# LIDO-HW_100_OutputStage.net
KiCad netlist of a schematic drawn in Altium Designer
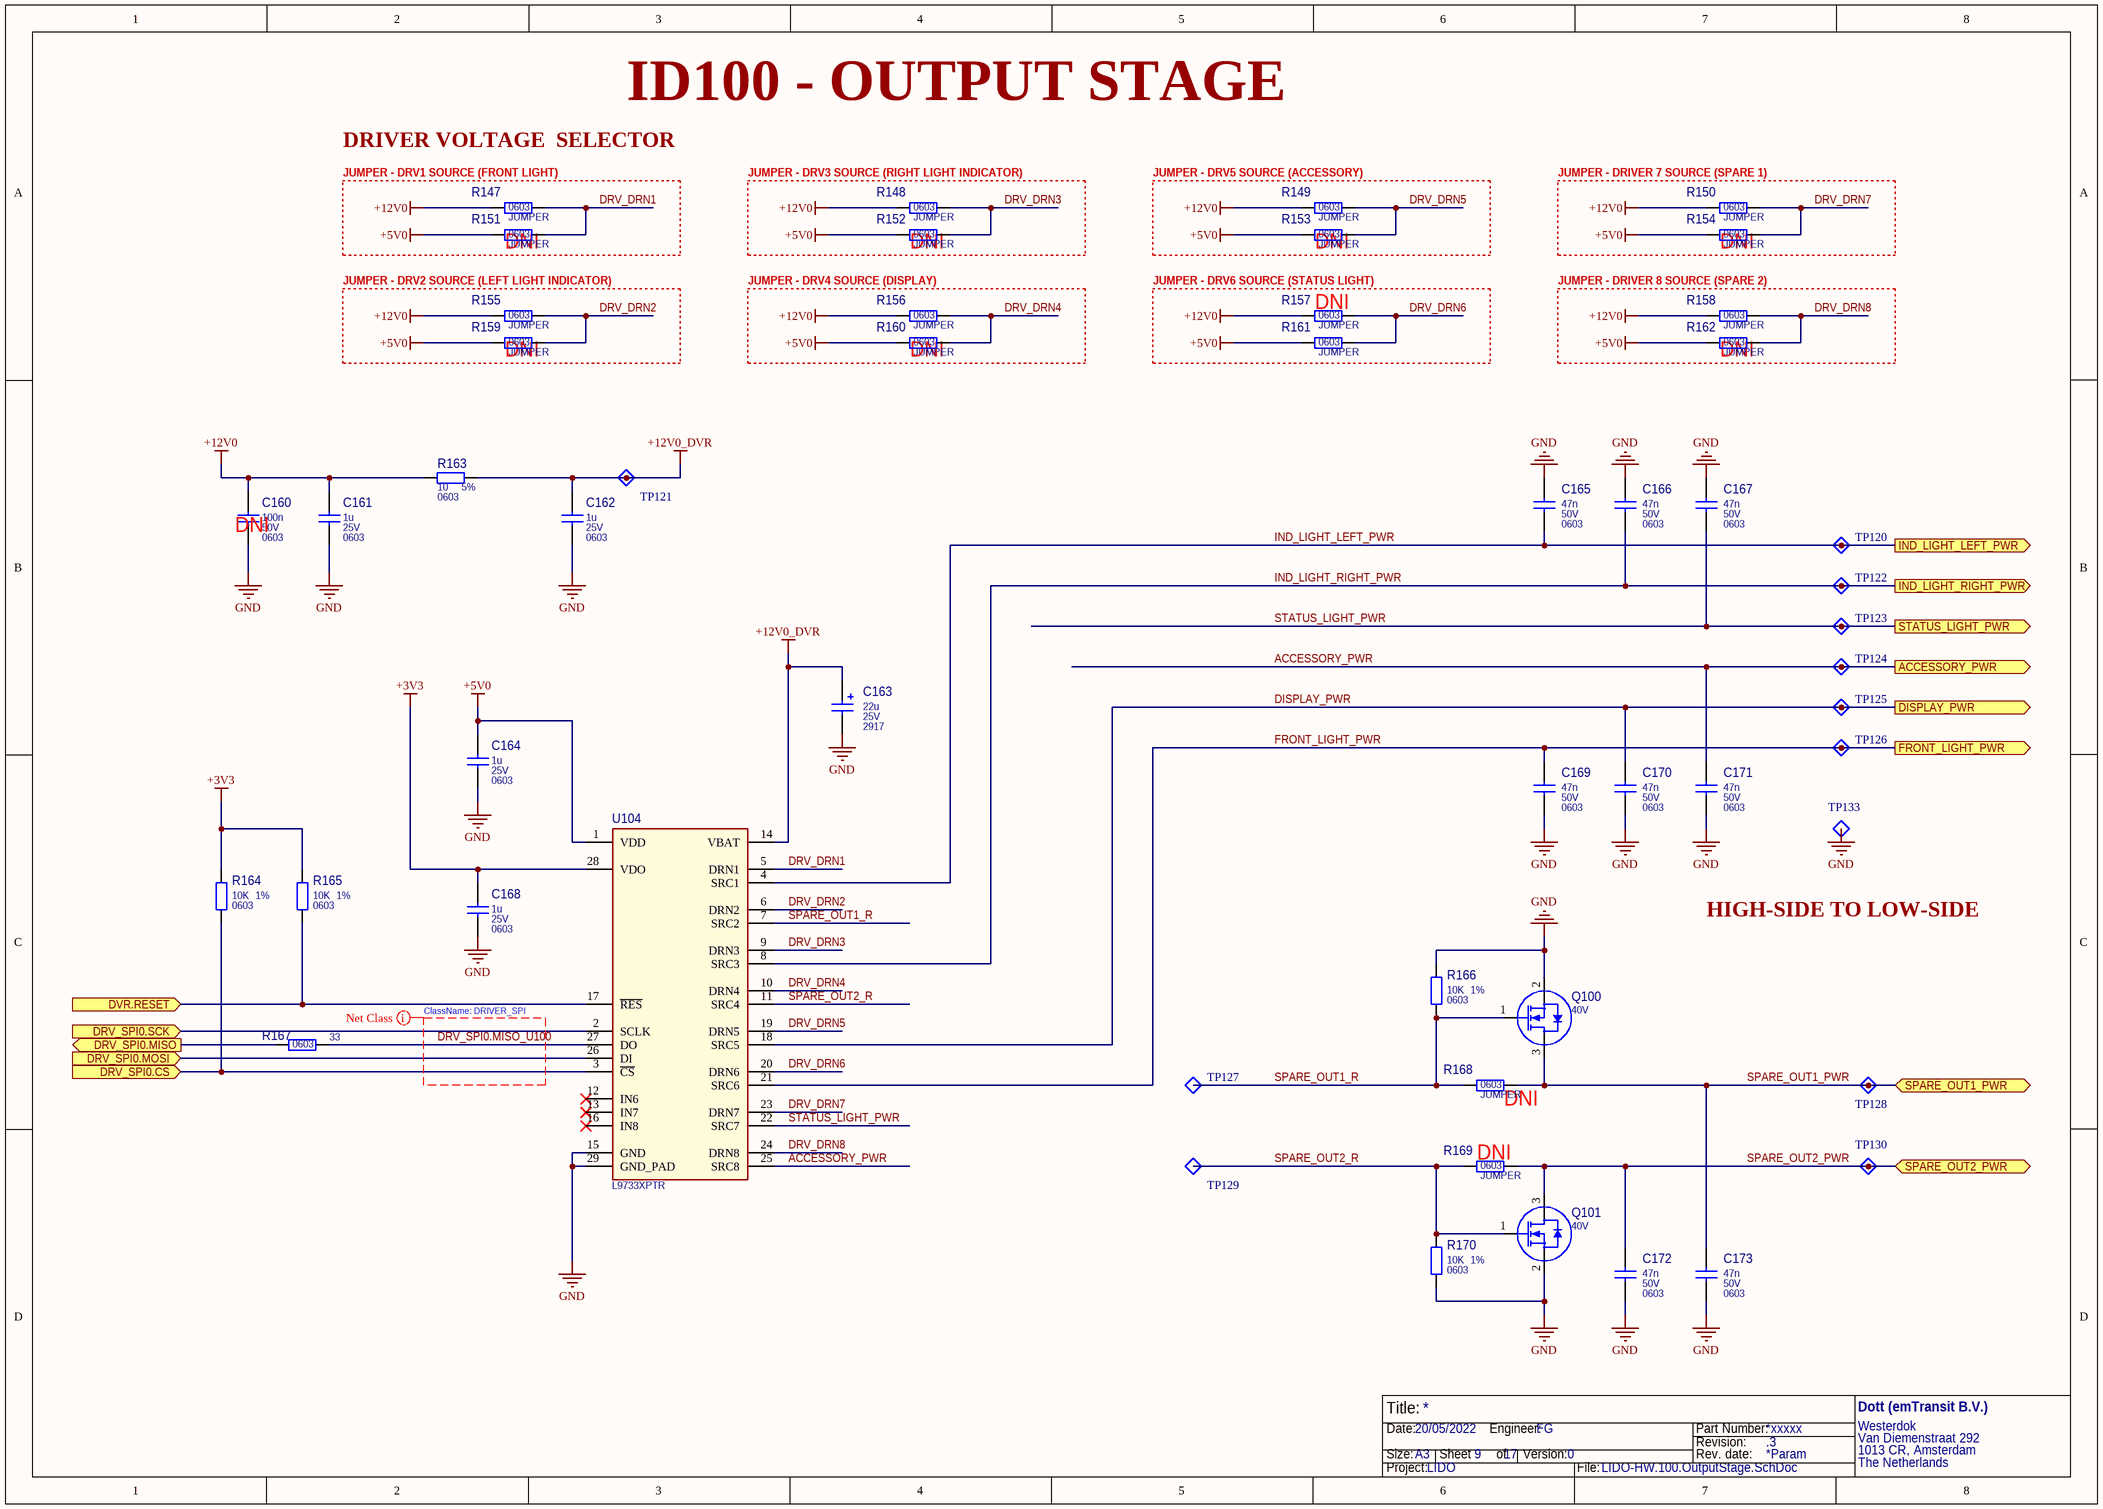
[diagram p0: LIDO-HW.100.OutputStage.SchDoc]

(export (version "E")
  (design (tool "Eeschema 10.0.6"))
  (components
    (comp (ref "C160")
      (value "100n")
      (footprint "CAP_0603_1608X90-N_MURATA_A")
      (description "CAP CER 0.1UF 50V X7R 0603")
      (fields
        (field (name "MANUFACTURER PART NUMBER") "CGA3E2X7R1H104K080AA")
        (field (name "MANUFACTURER") "TDK Corporation")
        (field (name "PART VALUE 2") "50V")
        (field (name "PART PACKAGE") "0603")
      )
      (libsource (lib "DB_Library") (part "Ceramic"))
    )
    (comp (ref "C161")
      (value "1u")
      (footprint "CAP_0603_1608X90-N_MURATA_A")
      (description "CAP CER 1UF 25V X7R 0603")
      (fields
        (field (name "MANUFACTURER PART NUMBER") "CGA3E1X7R1E105M080AE")
        (field (name "MANUFACTURER") "TDK Corporation")
        (field (name "PART VALUE 2") "25V")
        (field (name "PART PACKAGE") "0603")
      )
      (libsource (lib "DB_Library") (part "Ceramic"))
    )
    (comp (ref "C162")
      (value "1u")
      (footprint "CAP_0603_1608X90-N_MURATA_A")
      (description "CAP CER 1UF 25V X7R 0603")
      (fields
        (field (name "MANUFACTURER PART NUMBER") "CGA3E1X7R1E105M080AE")
        (field (name "MANUFACTURER") "TDK Corporation")
        (field (name "PART VALUE 2") "25V")
        (field (name "PART PACKAGE") "0603")
      )
      (libsource (lib "DB_Library") (part "Ceramic"))
    )
    (comp (ref "C163")
      (value "22u")
      (footprint "CAP_2917_7343X140-N_MURATA_A")
      (description "CAP ALUM POLY 22UF 20% 25V SMD")
      (fields
        (field (name "MANUFACTURER PART NUMBER") "ECASD31E226M040KA0")
        (field (name "MANUFACTURER") "Murata Electronics")
        (field (name "PART VALUE 2") "25V")
        (field (name "PART PACKAGE") "2917")
      )
      (libsource (lib "DB_Library") (part "Polarized"))
    )
    (comp (ref "C164")
      (value "1u")
      (footprint "CAP_0603_1608X90-N_MURATA_A")
      (description "CAP CER 1UF 25V X7R 0603")
      (fields
        (field (name "MANUFACTURER PART NUMBER") "CGA3E1X7R1E105M080AE")
        (field (name "MANUFACTURER") "TDK Corporation")
        (field (name "PART VALUE 2") "25V")
        (field (name "PART PACKAGE") "0603")
      )
      (libsource (lib "DB_Library") (part "Ceramic"))
    )
    (comp (ref "C165")
      (value "47n")
      (footprint "CAP_0603_1608X90-N_MURATA_A")
      (description "CAP CER 0.047UF 50V X7R 0603")
      (fields
        (field (name "MANUFACTURER PART NUMBER") "GCM188R71H473KA55D")
        (field (name "MANUFACTURER") "Murata Electronics")
        (field (name "PART VALUE 2") "50V")
        (field (name "PART PACKAGE") "0603")
      )
      (libsource (lib "DB_Library") (part "Ceramic"))
    )
    (comp (ref "C166")
      (value "47n")
      (footprint "CAP_0603_1608X90-N_MURATA_A")
      (description "CAP CER 0.047UF 50V X7R 0603")
      (fields
        (field (name "MANUFACTURER PART NUMBER") "GCM188R71H473KA55D")
        (field (name "MANUFACTURER") "Murata Electronics")
        (field (name "PART VALUE 2") "50V")
        (field (name "PART PACKAGE") "0603")
      )
      (libsource (lib "DB_Library") (part "Ceramic"))
    )
    (comp (ref "C167")
      (value "47n")
      (footprint "CAP_0603_1608X90-N_MURATA_A")
      (description "CAP CER 0.047UF 50V X7R 0603")
      (fields
        (field (name "MANUFACTURER PART NUMBER") "GCM188R71H473KA55D")
        (field (name "MANUFACTURER") "Murata Electronics")
        (field (name "PART VALUE 2") "50V")
        (field (name "PART PACKAGE") "0603")
      )
      (libsource (lib "DB_Library") (part "Ceramic"))
    )
    (comp (ref "C168")
      (value "1u")
      (footprint "CAP_0603_1608X90-N_MURATA_A")
      (description "CAP CER 1UF 25V X7R 0603")
      (fields
        (field (name "MANUFACTURER PART NUMBER") "CGA3E1X7R1E105M080AE")
        (field (name "MANUFACTURER") "TDK Corporation")
        (field (name "PART VALUE 2") "25V")
        (field (name "PART PACKAGE") "0603")
      )
      (libsource (lib "DB_Library") (part "Ceramic"))
    )
    (comp (ref "C169")
      (value "47n")
      (footprint "CAP_0603_1608X90-N_MURATA_A")
      (description "CAP CER 0.047UF 50V X7R 0603")
      (fields
        (field (name "MANUFACTURER PART NUMBER") "GCM188R71H473KA55D")
        (field (name "MANUFACTURER") "Murata Electronics")
        (field (name "PART VALUE 2") "50V")
        (field (name "PART PACKAGE") "0603")
      )
      (libsource (lib "DB_Library") (part "Ceramic"))
    )
    (comp (ref "C170")
      (value "47n")
      (footprint "CAP_0603_1608X90-N_MURATA_A")
      (description "CAP CER 0.047UF 50V X7R 0603")
      (fields
        (field (name "MANUFACTURER PART NUMBER") "GCM188R71H473KA55D")
        (field (name "MANUFACTURER") "Murata Electronics")
        (field (name "PART VALUE 2") "50V")
        (field (name "PART PACKAGE") "0603")
      )
      (libsource (lib "DB_Library") (part "Ceramic"))
    )
    (comp (ref "C171")
      (value "47n")
      (footprint "CAP_0603_1608X90-N_MURATA_A")
      (description "CAP CER 0.047UF 50V X7R 0603")
      (fields
        (field (name "MANUFACTURER PART NUMBER") "GCM188R71H473KA55D")
        (field (name "MANUFACTURER") "Murata Electronics")
        (field (name "PART VALUE 2") "50V")
        (field (name "PART PACKAGE") "0603")
      )
      (libsource (lib "DB_Library") (part "Ceramic"))
    )
    (comp (ref "C172")
      (value "47n")
      (footprint "CAP_0603_1608X90-N_MURATA_A")
      (description "CAP CER 0.047UF 50V X7R 0603")
      (fields
        (field (name "MANUFACTURER PART NUMBER") "GCM188R71H473KA55D")
        (field (name "MANUFACTURER") "Murata Electronics")
        (field (name "PART VALUE 2") "50V")
        (field (name "PART PACKAGE") "0603")
      )
      (libsource (lib "DB_Library") (part "Ceramic"))
    )
    (comp (ref "C173")
      (value "47n")
      (footprint "CAP_0603_1608X90-N_MURATA_A")
      (description "CAP CER 0.047UF 50V X7R 0603")
      (fields
        (field (name "MANUFACTURER PART NUMBER") "GCM188R71H473KA55D")
        (field (name "MANUFACTURER") "Murata Electronics")
        (field (name "PART VALUE 2") "50V")
        (field (name "PART PACKAGE") "0603")
      )
      (libsource (lib "DB_Library") (part "Ceramic"))
    )
    (comp (ref "Q100")
      (value "40V")
      (footprint "SOT23-3P95_237X112L60-N_ANALOG_A")
      (description "MOSFET N-CH 40V 4.6A SOT23")
      (fields
        (field (name "MANUFACTURER PART NUMBER") "DMN4035LQ-13")
        (field (name "MANUFACTURER") "Diodes Incorporated")
      )
      (libsource (lib "DB_Library") (part "MOSFET_N_WD_1G_2S_3D"))
    )
    (comp (ref "Q101")
      (value "40V")
      (footprint "SOT23-3P95_237X112L60-N_ANALOG_A")
      (description "MOSFET N-CH 40V 4.6A SOT23")
      (fields
        (field (name "MANUFACTURER PART NUMBER") "DMN4035LQ-13")
        (field (name "MANUFACTURER") "Diodes Incorporated")
      )
      (libsource (lib "DB_Library") (part "MOSFET_N_WD_1G_2S_3D"))
    )
    (comp (ref "R147")
      (value "JUMPER")
      (footprint "RES_0603_1608X60-N_YAGEO_A")
      (description "RES 0 OHM JUMPER 1/10W 0603")
      (fields
        (field (name "MANUFACTURER PART NUMBER") "RC0603JR-070RL")
        (field (name "MANUFACTURER") "YAGEO")
        (field (name "PART PACKAGE") "0603")
      )
      (libsource (lib "DB_Library") (part "Resistor"))
    )
    (comp (ref "R148")
      (value "JUMPER")
      (footprint "RES_0603_1608X60-N_YAGEO_A")
      (description "RES 0 OHM JUMPER 1/10W 0603")
      (fields
        (field (name "MANUFACTURER PART NUMBER") "RC0603JR-070RL")
        (field (name "MANUFACTURER") "YAGEO")
        (field (name "PART PACKAGE") "0603")
      )
      (libsource (lib "DB_Library") (part "Resistor"))
    )
    (comp (ref "R149")
      (value "JUMPER")
      (footprint "RES_0603_1608X60-N_YAGEO_A")
      (description "RES 0 OHM JUMPER 1/10W 0603")
      (fields
        (field (name "MANUFACTURER PART NUMBER") "RC0603JR-070RL")
        (field (name "MANUFACTURER") "YAGEO")
        (field (name "PART PACKAGE") "0603")
      )
      (libsource (lib "DB_Library") (part "Resistor"))
    )
    (comp (ref "R150")
      (value "JUMPER")
      (footprint "RES_0603_1608X60-N_YAGEO_A")
      (description "RES 0 OHM JUMPER 1/10W 0603")
      (fields
        (field (name "MANUFACTURER PART NUMBER") "RC0603JR-070RL")
        (field (name "MANUFACTURER") "YAGEO")
        (field (name "PART PACKAGE") "0603")
      )
      (libsource (lib "DB_Library") (part "Resistor"))
    )
    (comp (ref "R151")
      (value "JUMPER")
      (footprint "RES_0603_1608X60-N_YAGEO_A")
      (description "RES 0 OHM JUMPER 1/10W 0603")
      (fields
        (field (name "MANUFACTURER PART NUMBER") "RC0603JR-070RL")
        (field (name "MANUFACTURER") "YAGEO")
        (field (name "PART PACKAGE") "0603")
      )
      (libsource (lib "DB_Library") (part "Resistor"))
    )
    (comp (ref "R152")
      (value "JUMPER")
      (footprint "RES_0603_1608X60-N_YAGEO_A")
      (description "RES 0 OHM JUMPER 1/10W 0603")
      (fields
        (field (name "MANUFACTURER PART NUMBER") "RC0603JR-070RL")
        (field (name "MANUFACTURER") "YAGEO")
        (field (name "PART PACKAGE") "0603")
      )
      (libsource (lib "DB_Library") (part "Resistor"))
    )
    (comp (ref "R153")
      (value "JUMPER")
      (footprint "RES_0603_1608X60-N_YAGEO_A")
      (description "RES 0 OHM JUMPER 1/10W 0603")
      (fields
        (field (name "MANUFACTURER PART NUMBER") "RC0603JR-070RL")
        (field (name "MANUFACTURER") "YAGEO")
        (field (name "PART PACKAGE") "0603")
      )
      (libsource (lib "DB_Library") (part "Resistor"))
    )
    (comp (ref "R154")
      (value "JUMPER")
      (footprint "RES_0603_1608X60-N_YAGEO_A")
      (description "RES 0 OHM JUMPER 1/10W 0603")
      (fields
        (field (name "MANUFACTURER PART NUMBER") "RC0603JR-070RL")
        (field (name "MANUFACTURER") "YAGEO")
        (field (name "PART PACKAGE") "0603")
      )
      (libsource (lib "DB_Library") (part "Resistor"))
    )
    (comp (ref "R155")
      (value "JUMPER")
      (footprint "RES_0603_1608X60-N_YAGEO_A")
      (description "RES 0 OHM JUMPER 1/10W 0603")
      (fields
        (field (name "MANUFACTURER PART NUMBER") "RC0603JR-070RL")
        (field (name "MANUFACTURER") "YAGEO")
        (field (name "PART PACKAGE") "0603")
      )
      (libsource (lib "DB_Library") (part "Resistor"))
    )
    (comp (ref "R156")
      (value "JUMPER")
      (footprint "RES_0603_1608X60-N_YAGEO_A")
      (description "RES 0 OHM JUMPER 1/10W 0603")
      (fields
        (field (name "MANUFACTURER PART NUMBER") "RC0603JR-070RL")
        (field (name "MANUFACTURER") "YAGEO")
        (field (name "PART PACKAGE") "0603")
      )
      (libsource (lib "DB_Library") (part "Resistor"))
    )
    (comp (ref "R157")
      (value "JUMPER")
      (footprint "RES_0603_1608X60-N_YAGEO_A")
      (description "RES 0 OHM JUMPER 1/10W 0603")
      (fields
        (field (name "MANUFACTURER PART NUMBER") "RC0603JR-070RL")
        (field (name "MANUFACTURER") "YAGEO")
        (field (name "PART PACKAGE") "0603")
      )
      (libsource (lib "DB_Library") (part "Resistor"))
    )
    (comp (ref "R158")
      (value "JUMPER")
      (footprint "RES_0603_1608X60-N_YAGEO_A")
      (description "RES 0 OHM JUMPER 1/10W 0603")
      (fields
        (field (name "MANUFACTURER PART NUMBER") "RC0603JR-070RL")
        (field (name "MANUFACTURER") "YAGEO")
        (field (name "PART PACKAGE") "0603")
      )
      (libsource (lib "DB_Library") (part "Resistor"))
    )
    (comp (ref "R159")
      (value "JUMPER")
      (footprint "RES_0603_1608X60-N_YAGEO_A")
      (description "RES 0 OHM JUMPER 1/10W 0603")
      (fields
        (field (name "MANUFACTURER PART NUMBER") "RC0603JR-070RL")
        (field (name "MANUFACTURER") "YAGEO")
        (field (name "PART PACKAGE") "0603")
      )
      (libsource (lib "DB_Library") (part "Resistor"))
    )
    (comp (ref "R160")
      (value "JUMPER")
      (footprint "RES_0603_1608X60-N_YAGEO_A")
      (description "RES 0 OHM JUMPER 1/10W 0603")
      (fields
        (field (name "MANUFACTURER PART NUMBER") "RC0603JR-070RL")
        (field (name "MANUFACTURER") "YAGEO")
        (field (name "PART PACKAGE") "0603")
      )
      (libsource (lib "DB_Library") (part "Resistor"))
    )
    (comp (ref "R161")
      (value "JUMPER")
      (footprint "RES_0603_1608X60-N_YAGEO_A")
      (description "RES 0 OHM JUMPER 1/10W 0603")
      (fields
        (field (name "MANUFACTURER PART NUMBER") "RC0603JR-070RL")
        (field (name "MANUFACTURER") "YAGEO")
        (field (name "PART PACKAGE") "0603")
      )
      (libsource (lib "DB_Library") (part "Resistor"))
    )
    (comp (ref "R162")
      (value "JUMPER")
      (footprint "RES_0603_1608X60-N_YAGEO_A")
      (description "RES 0 OHM JUMPER 1/10W 0603")
      (fields
        (field (name "MANUFACTURER PART NUMBER") "RC0603JR-070RL")
        (field (name "MANUFACTURER") "YAGEO")
        (field (name "PART PACKAGE") "0603")
      )
      (libsource (lib "DB_Library") (part "Resistor"))
    )
    (comp (ref "R163")
      (value "10")
      (footprint "RES_0603_1608X60-N_YAGEO_A")
      (description "RES SMD 10 OHM 5% 1/4W 0603")
      (fields
        (field (name "MANUFACTURER PART NUMBER") "ESR03EZPJ100")
        (field (name "MANUFACTURER") "Rohm Semiconductor")
        (field (name "PART VALUE 2") "5%")
        (field (name "PART PACKAGE") "0603")
      )
      (libsource (lib "DB_Library") (part "Resistor"))
    )
    (comp (ref "R164")
      (value "10K")
      (footprint "RES_0603_1608X60-N_YAGEO_A")
      (description "RES 10K OHM 1% 1/10W 0603")
      (fields
        (field (name "MANUFACTURER PART NUMBER") "RC0603FR-0710KL")
        (field (name "MANUFACTURER") "YAGEO")
        (field (name "PART VALUE 2") "1%")
        (field (name "PART PACKAGE") "0603")
      )
      (libsource (lib "") (part "Resistor_1"))
    )
    (comp (ref "R165")
      (value "10K")
      (footprint "RES_0603_1608X60-N_YAGEO_A")
      (description "RES 10K OHM 1% 1/10W 0603")
      (fields
        (field (name "MANUFACTURER PART NUMBER") "RC0603FR-0710KL")
        (field (name "MANUFACTURER") "YAGEO")
        (field (name "PART VALUE 2") "1%")
        (field (name "PART PACKAGE") "0603")
      )
      (libsource (lib "") (part "Resistor_1"))
    )
    (comp (ref "R166")
      (value "10K")
      (footprint "RES_0603_1608X60-N_YAGEO_A")
      (description "RES 10K OHM 1% 1/10W 0603")
      (fields
        (field (name "MANUFACTURER PART NUMBER") "RC0603FR-0710KL")
        (field (name "MANUFACTURER") "YAGEO")
        (field (name "PART VALUE 2") "1%")
        (field (name "PART PACKAGE") "0603")
      )
      (libsource (lib "") (part "Resistor_1"))
    )
    (comp (ref "R167")
      (value "33")
      (footprint "RES_0603_1608X60-N_YAGEO_A")
      (description "RES 33 OHM 5% 1/10W 0603")
      (fields
        (field (name "MANUFACTURER PART NUMBER") "RC0603JR-0733RL")
        (field (name "MANUFACTURER") "YAGEO")
        (field (name "PART PACKAGE") "0603")
      )
      (libsource (lib "DB_Library") (part "Resistor"))
    )
    (comp (ref "R168")
      (value "JUMPER")
      (footprint "RES_0603_1608X60-N_YAGEO_A")
      (description "RES 0 OHM JUMPER 1/10W 0603")
      (fields
        (field (name "MANUFACTURER PART NUMBER") "RC0603JR-070RL")
        (field (name "MANUFACTURER") "YAGEO")
        (field (name "PART PACKAGE") "0603")
      )
      (libsource (lib "DB_Library") (part "Resistor"))
    )
    (comp (ref "R169")
      (value "JUMPER")
      (footprint "RES_0603_1608X60-N_YAGEO_A")
      (description "RES 0 OHM JUMPER 1/10W 0603")
      (fields
        (field (name "MANUFACTURER PART NUMBER") "RC0603JR-070RL")
        (field (name "MANUFACTURER") "YAGEO")
        (field (name "PART PACKAGE") "0603")
      )
      (libsource (lib "DB_Library") (part "Resistor"))
    )
    (comp (ref "R170")
      (value "10K")
      (footprint "RES_0603_1608X60-N_YAGEO_A")
      (description "RES 10K OHM 1% 1/10W 0603")
      (fields
        (field (name "MANUFACTURER PART NUMBER") "RC0603FR-0710KL")
        (field (name "MANUFACTURER") "YAGEO")
        (field (name "PART VALUE 2") "1%")
        (field (name "PART PACKAGE") "0603")
      )
      (libsource (lib "") (part "Resistor_1"))
    )
    (comp (ref "TP120")
      (value "TestPoint_A")
      (footprint "TESTPOINT_1D_A")
      (description "Pad Diamater 1mm")
      (fields (field (name "PART") "Test Point 1D A") (field (name "OBSOLETE PART") "False"))
      (libsource (lib "DB_Library") (part "TestPoint_A"))
    )
    (comp (ref "TP121")
      (value "TestPoint_A")
      (footprint "TESTPOINT_1D_A")
      (description "Pad Diamater 1mm")
      (fields (field (name "PART") "Test Point 1D A") (field (name "OBSOLETE PART") "False"))
      (libsource (lib "DB_Library") (part "TestPoint_A"))
    )
    (comp (ref "TP122")
      (value "TestPoint_A")
      (footprint "TESTPOINT_1D_A")
      (description "Pad Diamater 1mm")
      (fields (field (name "PART") "Test Point 1D A") (field (name "OBSOLETE PART") "False"))
      (libsource (lib "DB_Library") (part "TestPoint_A"))
    )
    (comp (ref "TP123")
      (value "TestPoint_A")
      (footprint "TESTPOINT_1D_A")
      (description "Pad Diamater 1mm")
      (fields (field (name "PART") "Test Point 1D A") (field (name "OBSOLETE PART") "False"))
      (libsource (lib "DB_Library") (part "TestPoint_A"))
    )
    (comp (ref "TP124")
      (value "TestPoint_A")
      (footprint "TESTPOINT_1D_A")
      (description "Pad Diamater 1mm")
      (fields (field (name "PART") "Test Point 1D A") (field (name "OBSOLETE PART") "False"))
      (libsource (lib "DB_Library") (part "TestPoint_A"))
    )
    (comp (ref "TP125")
      (value "TestPoint_A")
      (footprint "TESTPOINT_1D_A")
      (description "Pad Diamater 1mm")
      (fields (field (name "PART") "Test Point 1D A") (field (name "OBSOLETE PART") "False"))
      (libsource (lib "DB_Library") (part "TestPoint_A"))
    )
    (comp (ref "TP126")
      (value "TestPoint_A")
      (footprint "TESTPOINT_1D_A")
      (description "Pad Diamater 1mm")
      (fields (field (name "PART") "Test Point 1D A") (field (name "OBSOLETE PART") "False"))
      (libsource (lib "DB_Library") (part "TestPoint_A"))
    )
    (comp (ref "TP127")
      (value "TestPoint_A")
      (footprint "TESTPOINT_1D_A")
      (description "Pad Diamater 1mm")
      (fields (field (name "PART") "Test Point 1D A") (field (name "OBSOLETE PART") "False"))
      (libsource (lib "DB_Library") (part "TestPoint_A"))
    )
    (comp (ref "TP128")
      (value "TestPoint_A")
      (footprint "TESTPOINT_1D_A")
      (description "Pad Diamater 1mm")
      (fields (field (name "PART") "Test Point 1D A") (field (name "OBSOLETE PART") "False"))
      (libsource (lib "DB_Library") (part "TestPoint_A"))
    )
    (comp (ref "TP129")
      (value "TestPoint_A")
      (footprint "TESTPOINT_1D_A")
      (description "Pad Diamater 1mm")
      (fields (field (name "PART") "Test Point 1D A") (field (name "OBSOLETE PART") "False"))
      (libsource (lib "DB_Library") (part "TestPoint_A"))
    )
    (comp (ref "TP130")
      (value "TestPoint_A")
      (footprint "TESTPOINT_1D_A")
      (description "Pad Diamater 1mm")
      (fields (field (name "PART") "Test Point 1D A") (field (name "OBSOLETE PART") "False"))
      (libsource (lib "DB_Library") (part "TestPoint_A"))
    )
    (comp (ref "TP133")
      (value "TestPoint_A")
      (footprint "TESTPOINT_1D_A")
      (description "Pad Diamater 1mm")
      (fields (field (name "PART") "Test Point 1D A") (field (name "OBSOLETE PART") "False"))
      (libsource (lib "DB_Library") (part "TestPoint_A"))
    )
    (comp (ref "U104")
      (value "L9733XPTR")
      (footprint "SSOP29P65_1030X1030X245L80X27-N_ST_A")
      (description "Power Switch/Driver 1:8 N-Channel 1A PowerSSO-28 Exposed Pad")
      (fields (field (name "MANUFACTURER") "STMicroelectronics") (field (name "OBSOLETE PART") "False"))
      (libsource (lib "DB_Library") (part "L9733_A"))
    )
  )
  (nets
    (net (code "1") (name "+3V3") (class "Default")
      (node (ref "C168") (pin "1") (pinfunction "1_1") (pintype "passive"))
      (node (ref "R164") (pin "2") (pinfunction "2_2") (pintype "passive"))
      (node (ref "R165") (pin "2") (pinfunction "2_2") (pintype "passive"))
      (node (ref "U104") (pin "28") (pinfunction "VDO_28") (pintype "passive"))
    )
    (net (code "2") (name "+5V0") (class "Default")
      (node (ref "C164") (pin "1") (pinfunction "1_1") (pintype "passive"))
      (node (ref "R151") (pin "1") (pinfunction "1_1") (pintype "passive"))
      (node (ref "R152") (pin "1") (pinfunction "1_1") (pintype "passive"))
      (node (ref "R153") (pin "1") (pinfunction "1_1") (pintype "passive"))
      (node (ref "R154") (pin "1") (pinfunction "1_1") (pintype "passive"))
      (node (ref "R159") (pin "1") (pinfunction "1_1") (pintype "passive"))
      (node (ref "R160") (pin "1") (pinfunction "1_1") (pintype "passive"))
      (node (ref "R161") (pin "1") (pinfunction "1_1") (pintype "passive"))
      (node (ref "R162") (pin "1") (pinfunction "1_1") (pintype "passive"))
      (node (ref "U104") (pin "1") (pinfunction "VDD_1") (pintype "power_in"))
    )
    (net (code "3") (name "+12V0") (class "Default")
      (node (ref "C160") (pin "2") (pinfunction "2_2") (pintype "passive"))
      (node (ref "C161") (pin "1") (pinfunction "1_1") (pintype "passive"))
      (node (ref "R147") (pin "1") (pinfunction "1_1") (pintype "passive"))
      (node (ref "R148") (pin "1") (pinfunction "1_1") (pintype "passive"))
      (node (ref "R149") (pin "1") (pinfunction "1_1") (pintype "passive"))
      (node (ref "R150") (pin "1") (pinfunction "1_1") (pintype "passive"))
      (node (ref "R155") (pin "1") (pinfunction "1_1") (pintype "passive"))
      (node (ref "R156") (pin "1") (pinfunction "1_1") (pintype "passive"))
      (node (ref "R157") (pin "1") (pinfunction "1_1") (pintype "passive"))
      (node (ref "R158") (pin "1") (pinfunction "1_1") (pintype "passive"))
      (node (ref "R163") (pin "1") (pinfunction "1_1") (pintype "passive"))
    )
    (net (code "4") (name "+12V0_DVR") (class "Default")
      (node (ref "C162") (pin "1") (pinfunction "1_1") (pintype "passive"))
      (node (ref "C163") (pin "1") (pinfunction "1_1") (pintype "passive"))
      (node (ref "R163") (pin "2") (pinfunction "2_2") (pintype "passive"))
      (node (ref "TP121") (pin "1") (pinfunction "TP_1") (pintype "passive"))
      (node (ref "U104") (pin "14") (pinfunction "VBAT_14") (pintype "power_in"))
    )
    (net (code "5") (name "/ACCESSORY_PWR") (class "Default")
      (node (ref "C171") (pin "1") (pinfunction "1_1") (pintype "passive"))
      (node (ref "TP124") (pin "1") (pinfunction "TP_1") (pintype "passive"))
      (node (ref "U104") (pin "25") (pinfunction "SRC8_25") (pintype "passive"))
    )
    (net (code "6") (name "/DISPLAY_PWR") (class "Default")
      (node (ref "C170") (pin "1") (pinfunction "1_1") (pintype "passive"))
      (node (ref "TP125") (pin "1") (pinfunction "TP_1") (pintype "passive"))
      (node (ref "U104") (pin "18") (pinfunction "SRC5_18") (pintype "passive"))
    )
    (net (code "7") (name "/DRV_DRN1") (class "Default")
      (node (ref "R147") (pin "2") (pinfunction "2_2") (pintype "passive"))
      (node (ref "R151") (pin "2") (pinfunction "2_2") (pintype "passive"))
      (node (ref "U104") (pin "5") (pinfunction "DRN1_5") (pintype "passive"))
    )
    (net (code "8") (name "/DRV_DRN2") (class "Default")
      (node (ref "R155") (pin "2") (pinfunction "2_2") (pintype "passive"))
      (node (ref "R159") (pin "2") (pinfunction "2_2") (pintype "passive"))
      (node (ref "U104") (pin "6") (pinfunction "DRN2_6") (pintype "passive"))
    )
    (net (code "9") (name "/DRV_DRN3") (class "Default")
      (node (ref "R148") (pin "2") (pinfunction "2_2") (pintype "passive"))
      (node (ref "R152") (pin "2") (pinfunction "2_2") (pintype "passive"))
      (node (ref "U104") (pin "9") (pinfunction "DRN3_9") (pintype "passive"))
    )
    (net (code "10") (name "/DRV_DRN4") (class "Default")
      (node (ref "R156") (pin "2") (pinfunction "2_2") (pintype "passive"))
      (node (ref "R160") (pin "2") (pinfunction "2_2") (pintype "passive"))
      (node (ref "U104") (pin "10") (pinfunction "DRN4_10") (pintype "passive"))
    )
    (net (code "11") (name "/DRV_DRN5") (class "Default")
      (node (ref "R149") (pin "2") (pinfunction "2_2") (pintype "passive"))
      (node (ref "R153") (pin "2") (pinfunction "2_2") (pintype "passive"))
      (node (ref "U104") (pin "19") (pinfunction "DRN5_19") (pintype "passive"))
    )
    (net (code "12") (name "/DRV_DRN6") (class "Default")
      (node (ref "R157") (pin "2") (pinfunction "2_2") (pintype "passive"))
      (node (ref "R161") (pin "2") (pinfunction "2_2") (pintype "passive"))
      (node (ref "U104") (pin "20") (pinfunction "DRN6_20") (pintype "passive"))
    )
    (net (code "13") (name "/DRV_DRN7") (class "Default")
      (node (ref "R150") (pin "2") (pinfunction "2_2") (pintype "passive"))
      (node (ref "R154") (pin "2") (pinfunction "2_2") (pintype "passive"))
      (node (ref "U104") (pin "23") (pinfunction "DRN7_23") (pintype "passive"))
    )
    (net (code "14") (name "/DRV_DRN8") (class "Default")
      (node (ref "R158") (pin "2") (pinfunction "2_2") (pintype "passive"))
      (node (ref "R162") (pin "2") (pinfunction "2_2") (pintype "passive"))
      (node (ref "U104") (pin "24") (pinfunction "DRN8_24") (pintype "passive"))
    )
    (net (code "15") (name "/DRV_SPI0.CS") (class "Default")
      (node (ref "R164") (pin "1") (pinfunction "1_1") (pintype "passive"))
      (node (ref "U104") (pin "3") (pinfunction "~{CS}_3") (pintype "passive"))
    )
    (net (code "16") (name "/DRV_SPI0.MISO") (class "Default")
      (node (ref "R167") (pin "1") (pinfunction "1_1") (pintype "passive"))
    )
    (net (code "17") (name "/DRV_SPI0.MISO_U100") (class "Default")
      (node (ref "R167") (pin "2") (pinfunction "2_2") (pintype "passive"))
      (node (ref "U104") (pin "27") (pinfunction "DO_27") (pintype "passive"))
    )
    (net (code "18") (name "/DRV_SPI0.MOSI") (class "Default")
      (node (ref "U104") (pin "26") (pinfunction "DI_26") (pintype "passive"))
    )
    (net (code "19") (name "/DRV_SPI0.SCK") (class "Default")
      (node (ref "U104") (pin "2") (pinfunction "SCLK_2") (pintype "passive"))
    )
    (net (code "20") (name "/DVR.RESET") (class "Default")
      (node (ref "R165") (pin "1") (pinfunction "1_1") (pintype "passive"))
      (node (ref "U104") (pin "17") (pinfunction "~{RES}_17") (pintype "passive"))
    )
    (net (code "21") (name "/FRONT_LIGHT_PWR") (class "Default")
      (node (ref "C169") (pin "1") (pinfunction "1_1") (pintype "passive"))
      (node (ref "TP126") (pin "1") (pinfunction "TP_1") (pintype "passive"))
      (node (ref "U104") (pin "21") (pinfunction "SRC6_21") (pintype "passive"))
    )
    (net (code "22") (name "/IND_LIGHT_LEFT_PWR") (class "Default")
      (node (ref "C165") (pin "2") (pinfunction "2_2") (pintype "passive"))
      (node (ref "TP120") (pin "1") (pinfunction "TP_1") (pintype "passive"))
      (node (ref "U104") (pin "4") (pinfunction "SRC1_4") (pintype "passive"))
    )
    (net (code "23") (name "/IND_LIGHT_RIGHT_PWR") (class "Default")
      (node (ref "C166") (pin "2") (pinfunction "2_2") (pintype "passive"))
      (node (ref "TP122") (pin "1") (pinfunction "TP_1") (pintype "passive"))
      (node (ref "U104") (pin "8") (pinfunction "SRC3_8") (pintype "passive"))
    )
    (net (code "24") (name "/SPARE_OUT1_PWR") (class "Default")
      (node (ref "C173") (pin "1") (pinfunction "1_1") (pintype "passive"))
      (node (ref "Q100") (pin "3") (pinfunction "D_3") (pintype "passive"))
      (node (ref "R168") (pin "2") (pinfunction "2_2") (pintype "passive"))
      (node (ref "TP128") (pin "1") (pinfunction "TP_1") (pintype "passive"))
    )
    (net (code "25") (name "/SPARE_OUT1_R") (class "Default")
      (node (ref "Q100") (pin "1") (pinfunction "G_1") (pintype "passive"))
      (node (ref "R166") (pin "1") (pinfunction "1_1") (pintype "passive"))
      (node (ref "R168") (pin "1") (pinfunction "1_1") (pintype "passive"))
      (node (ref "TP127") (pin "1") (pinfunction "TP_1") (pintype "passive"))
      (node (ref "U104") (pin "7") (pinfunction "SRC2_7") (pintype "passive"))
    )
    (net (code "26") (name "/SPARE_OUT2_PWR") (class "Default")
      (node (ref "C172") (pin "1") (pinfunction "1_1") (pintype "passive"))
      (node (ref "Q101") (pin "3") (pinfunction "D_3") (pintype "passive"))
      (node (ref "R169") (pin "2") (pinfunction "2_2") (pintype "passive"))
      (node (ref "TP130") (pin "1") (pinfunction "TP_1") (pintype "passive"))
    )
    (net (code "27") (name "/SPARE_OUT2_R") (class "Default")
      (node (ref "Q101") (pin "1") (pinfunction "G_1") (pintype "passive"))
      (node (ref "R169") (pin "1") (pinfunction "1_1") (pintype "passive"))
      (node (ref "R170") (pin "2") (pinfunction "2_2") (pintype "passive"))
      (node (ref "TP129") (pin "1") (pinfunction "TP_1") (pintype "passive"))
      (node (ref "U104") (pin "11") (pinfunction "SRC4_11") (pintype "passive"))
    )
    (net (code "28") (name "/STATUS_LIGHT_PWR") (class "Default")
      (node (ref "C167") (pin "2") (pinfunction "2_2") (pintype "passive"))
      (node (ref "TP123") (pin "1") (pinfunction "TP_1") (pintype "passive"))
      (node (ref "U104") (pin "22") (pinfunction "SRC7_22") (pintype "passive"))
    )
    (net (code "29") (name "GND") (class "Default")
      (node (ref "C160") (pin "1") (pinfunction "1_1") (pintype "passive"))
      (node (ref "C161") (pin "2") (pinfunction "2_2") (pintype "passive"))
      (node (ref "C162") (pin "2") (pinfunction "2_2") (pintype "passive"))
      (node (ref "C163") (pin "2") (pinfunction "2_2") (pintype "passive"))
      (node (ref "C164") (pin "2") (pinfunction "2_2") (pintype "passive"))
      (node (ref "C165") (pin "1") (pinfunction "1_1") (pintype "passive"))
      (node (ref "C166") (pin "1") (pinfunction "1_1") (pintype "passive"))
      (node (ref "C167") (pin "1") (pinfunction "1_1") (pintype "passive"))
      (node (ref "C168") (pin "2") (pinfunction "2_2") (pintype "passive"))
      (node (ref "C169") (pin "2") (pinfunction "2_2") (pintype "passive"))
      (node (ref "C170") (pin "2") (pinfunction "2_2") (pintype "passive"))
      (node (ref "C171") (pin "2") (pinfunction "2_2") (pintype "passive"))
      (node (ref "C172") (pin "2") (pinfunction "2_2") (pintype "passive"))
      (node (ref "C173") (pin "2") (pinfunction "2_2") (pintype "passive"))
      (node (ref "Q100") (pin "2") (pinfunction "S_2") (pintype "passive"))
      (node (ref "Q101") (pin "2") (pinfunction "S_2") (pintype "passive"))
      (node (ref "R166") (pin "2") (pinfunction "2_2") (pintype "passive"))
      (node (ref "R170") (pin "1") (pinfunction "1_1") (pintype "passive"))
      (node (ref "TP133") (pin "1") (pinfunction "TP_1") (pintype "passive"))
      (node (ref "U104") (pin "15") (pinfunction "GND_15") (pintype "power_in"))
      (node (ref "U104") (pin "29") (pinfunction "GND_PAD_29") (pintype "power_in"))
    )
    (net (code "30") (name "unconnected-(U104-IN6-Pad12)") (class "Default")
      (node (ref "U104") (pin "12") (pinfunction "IN6_12") (pintype "passive+no_connect"))
    )
    (net (code "31") (name "unconnected-(U104-IN7-Pad13)") (class "Default")
      (node (ref "U104") (pin "13") (pinfunction "IN7_13") (pintype "passive+no_connect"))
    )
    (net (code "32") (name "unconnected-(U104-IN8-Pad16)") (class "Default")
      (node (ref "U104") (pin "16") (pinfunction "IN8_16") (pintype "passive+no_connect"))
    )
  )
)
